# OpenBook_Schematic.net
KiCad netlist of a schematic drawn in EAGLE
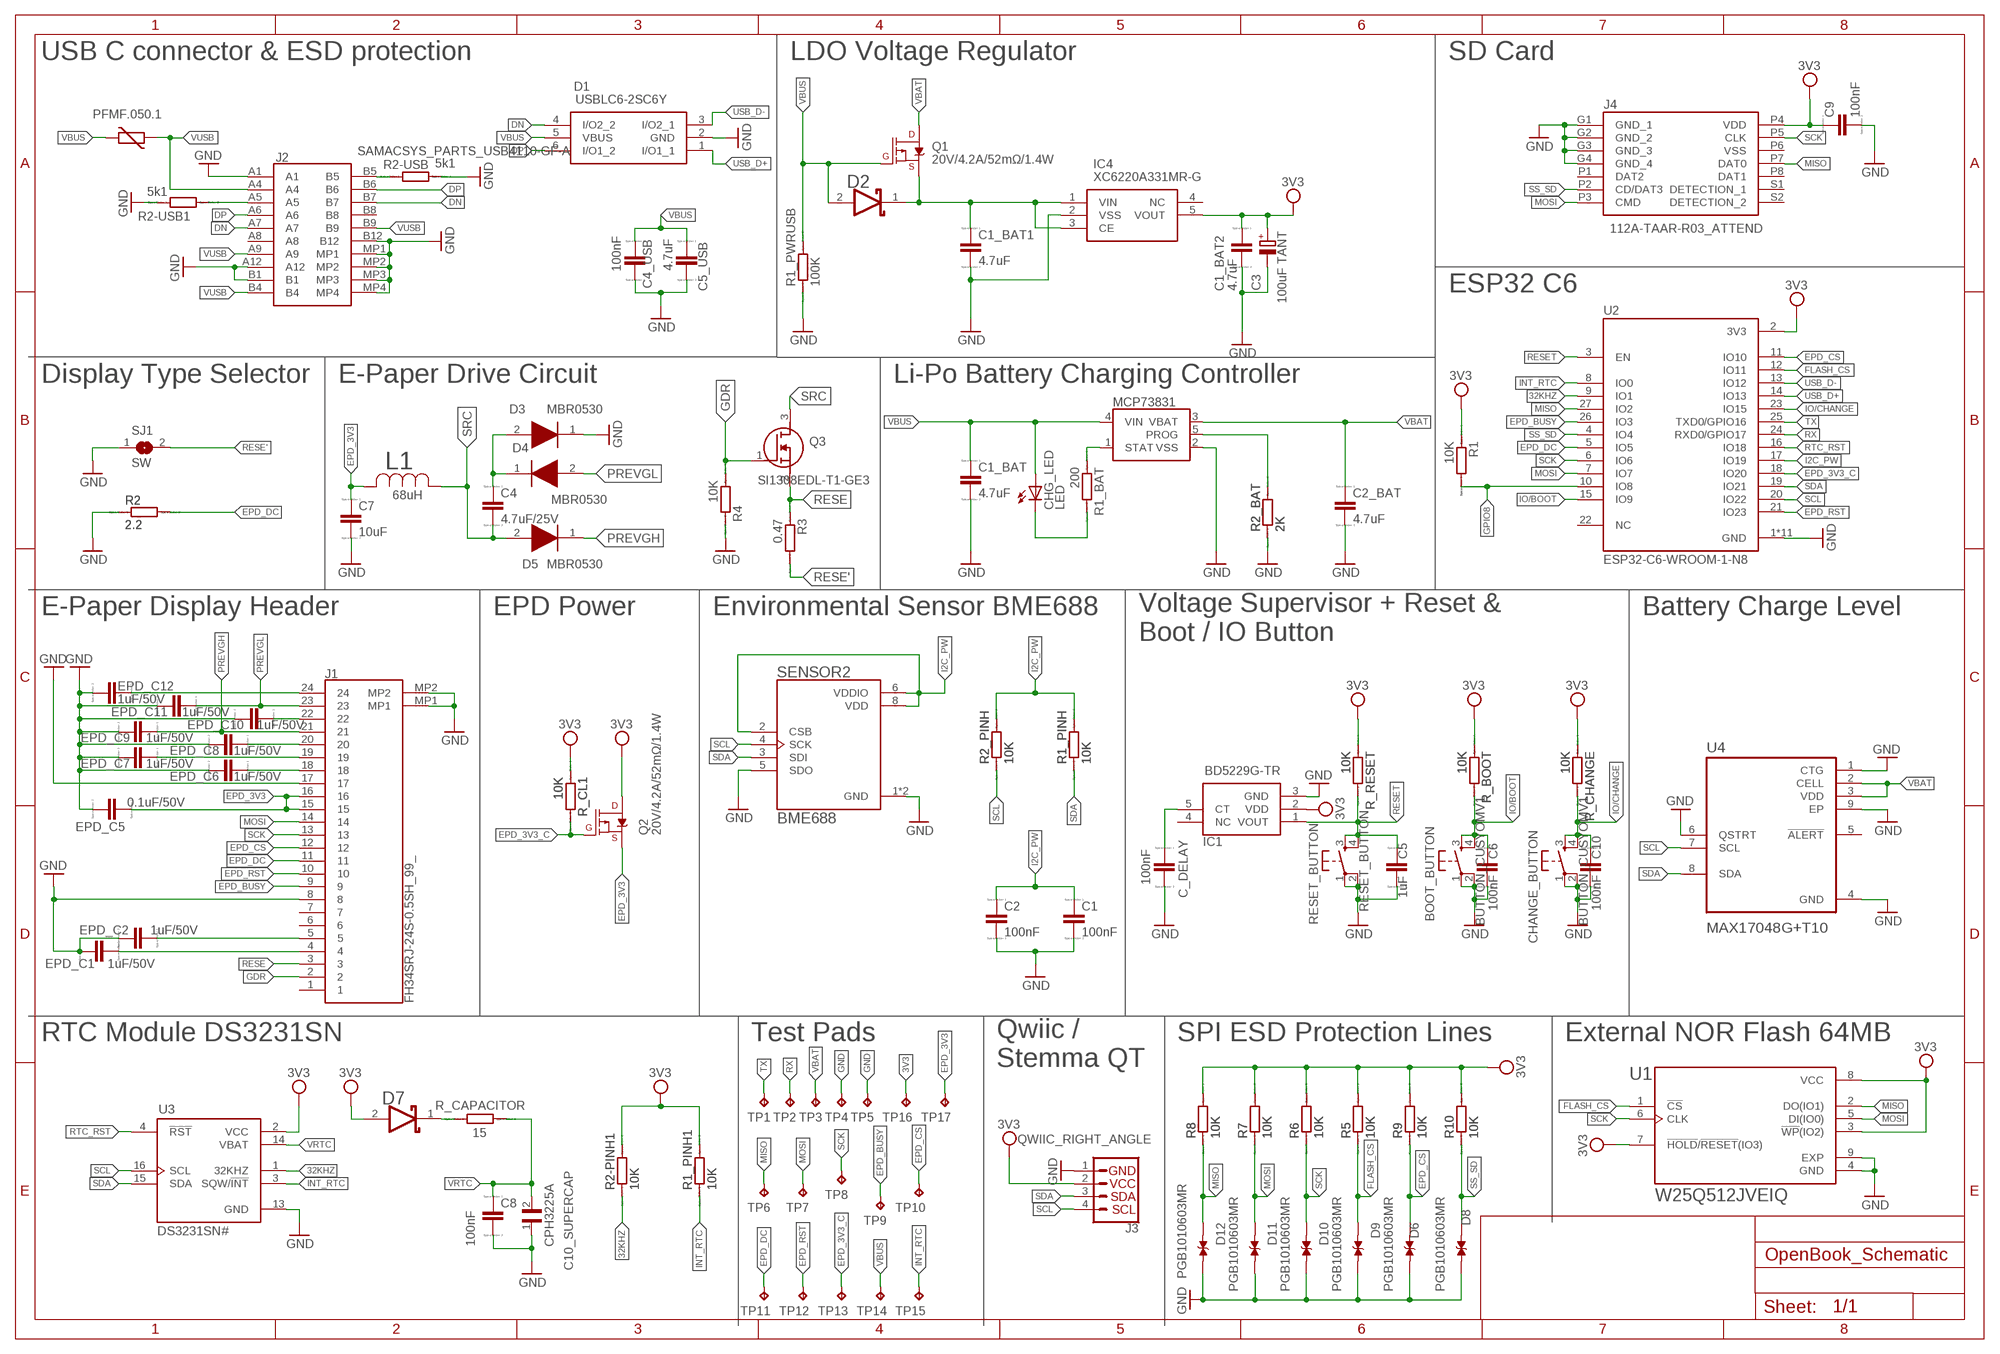
[diagram p0: schematic, sheet 1]

(export (version "E")
  (design (tool "Eeschema 10.0.6"))
  (components
    (comp (ref "BOOT_BUTTON")
      (value "BUTTON_CUSYOMV1")
      (footprint "eagle-import:MYBUTTON")
      (libsource (lib "eagle-import") (part "BUTTON_CUSYOMV1"))
    )
    (comp (ref "C1")
      (value "100nF")
      (footprint "eagle-import:EAGLE-LTSPICE_C0402")
      (libsource (lib "eagle-import") (part "EAGLE-LTSPICE_CC0402"))
    )
    (comp (ref "C1_BAT")
      (value "4.7uF")
      (footprint "eagle-import:EAGLE-LTSPICE_C0402")
      (libsource (lib "eagle-import") (part "EAGLE-LTSPICE_CC0402"))
    )
    (comp (ref "C1_BAT1")
      (value "4.7uF")
      (footprint "eagle-import:EAGLE-LTSPICE_C0402")
      (libsource (lib "eagle-import") (part "EAGLE-LTSPICE_CC0402"))
    )
    (comp (ref "C1_BAT2")
      (value "4.7uF")
      (footprint "eagle-import:EAGLE-LTSPICE_C0402")
      (libsource (lib "eagle-import") (part "EAGLE-LTSPICE_CC0402"))
    )
    (comp (ref "C2")
      (value "100nF")
      (footprint "eagle-import:EAGLE-LTSPICE_C0402")
      (libsource (lib "eagle-import") (part "EAGLE-LTSPICE_CC0402"))
    )
    (comp (ref "C2_BAT")
      (value "4.7uF")
      (footprint "eagle-import:EAGLE-LTSPICE_C0402")
      (libsource (lib "eagle-import") (part "EAGLE-LTSPICE_CC0402"))
    )
    (comp (ref "C3")
      (value "100uF TANT")
      (footprint "eagle-import:RCL_CT3528")
      (libsource (lib "eagle-import") (part "RCL_CPOL-EUCT3528"))
    )
    (comp (ref "C4")
      (value "4.7uF/25V")
      (footprint "eagle-import:EAGLE-LTSPICE_C0402")
      (libsource (lib "eagle-import") (part "EAGLE-LTSPICE_CC0402"))
    )
    (comp (ref "C4_USB")
      (value "100nF")
      (footprint "eagle-import:EAGLE-LTSPICE_C0402")
      (libsource (lib "eagle-import") (part "EAGLE-LTSPICE_CC0402"))
    )
    (comp (ref "C5")
      (value "1uF")
      (footprint "eagle-import:EAGLE-LTSPICE_C0402")
      (libsource (lib "eagle-import") (part "EAGLE-LTSPICE_CC0402"))
    )
    (comp (ref "C5_USB")
      (value "4.7uF")
      (footprint "eagle-import:EAGLE-LTSPICE_C0402")
      (libsource (lib "eagle-import") (part "EAGLE-LTSPICE_CC0402"))
    )
    (comp (ref "C6")
      (value "100nF")
      (footprint "eagle-import:EAGLE-LTSPICE_C0402")
      (libsource (lib "eagle-import") (part "EAGLE-LTSPICE_CC0402"))
    )
    (comp (ref "C7")
      (value "10uF")
      (footprint "eagle-import:EAGLE-LTSPICE_C0402")
      (libsource (lib "eagle-import") (part "EAGLE-LTSPICE_CC0402"))
    )
    (comp (ref "C8")
      (value "100nF")
      (footprint "eagle-import:EAGLE-LTSPICE_C0402")
      (libsource (lib "eagle-import") (part "EAGLE-LTSPICE_CC0402"))
    )
    (comp (ref "C9")
      (value "100nF")
      (footprint "eagle-import:EAGLE-LTSPICE_C0402")
      (libsource (lib "eagle-import") (part "EAGLE-LTSPICE_CC0402"))
    )
    (comp (ref "C10")
      (value "100nF")
      (footprint "eagle-import:EAGLE-LTSPICE_C0402")
      (libsource (lib "eagle-import") (part "EAGLE-LTSPICE_CC0402"))
    )
    (comp (ref "C10_SUPERCAP")
      (value "CPH3225A")
      (footprint "eagle-import:CAPCP3225X100N")
      (fields (field (name "MF") "Seiko Instruments"))
      (libsource (lib "eagle-import") (part "CPH3225A"))
    )
    (comp (ref "CHANGE_BUTTON")
      (value "BUTTON_CUSYOMV1")
      (footprint "eagle-import:MYBUTTON")
      (libsource (lib "eagle-import") (part "BUTTON_CUSYOMV1"))
    )
    (comp (ref "CHG_LED")
      (value "LED")
      (footprint "eagle-import:ADAFRUIT_CHIP-LED0603")
      (libsource (lib "eagle-import") (part "ADAFRUIT_LEDCHIP-LED0603"))
    )
    (comp (ref "C_DELAY")
      (value "100nF")
      (footprint "eagle-import:EAGLE-LTSPICE_C0402")
      (libsource (lib "eagle-import") (part "EAGLE-LTSPICE_CC0402"))
    )
    (comp (ref "D1")
      (value "USBLC6-2SC6Y")
      (footprint "eagle-import:SOT95P280X145-6N")
      (fields (field (name "MF") "STMicroelectronics"))
      (libsource (lib "eagle-import") (part "USBLC6-2SC6Y"))
    )
    (comp (ref "D2")
      (value "ESP32_WROVER_AVX---SD0805S020S1R0_AVX_SD0805S020S1R0_0_0AVX_SD0805S020S1R0_0_0")
      (footprint "eagle-import:ESP32_WROVER_AVX---SD0805S020S1R0_AVX_SD0805S020S1R0_0")
      (fields
        (field (name "DIGIKEY_PART_NUMBER") "478-7800-1-ND")
        (field (name "MF") "AVX")
        (field (name "MOUSER_PART_NUMBER") "581-SD0805S020S1R0")
      )
      (libsource (lib "eagle-import") (part "ESP32_WROVER_AVX---SD0805S020S1R0_AVX_SD0805S020S1R0_0_0AVX_SD0805S020S1R0_0_0"))
    )
    (comp (ref "D3")
      (value "MBR0530")
      (footprint "eagle-import:SOD3716X135N")
      (fields (field (name "MF") "ON Semiconductor"))
      (libsource (lib "eagle-import") (part "MBR0530"))
    )
    (comp (ref "D4")
      (value "MBR0530")
      (footprint "eagle-import:SOD3716X135N")
      (fields (field (name "MF") "ON Semiconductor"))
      (libsource (lib "eagle-import") (part "MBR0530"))
    )
    (comp (ref "D5")
      (value "MBR0530")
      (footprint "eagle-import:SOD3716X135N")
      (fields (field (name "MF") "ON Semiconductor"))
      (libsource (lib "eagle-import") (part "MBR0530"))
    )
    (comp (ref "D6")
      (value "PGB1010603MR")
      (footprint "eagle-import:DIOC1608X36N")
      (fields (field (name "MF") "Littelfuse Inc."))
      (libsource (lib "eagle-import") (part "PGB1010603MR"))
    )
    (comp (ref "D7")
      (value "ESP32_WROVER_AVX---SD0805S020S1R0_AVX_SD0805S020S1R0_0_0AVX_SD0805S020S1R0_0_0")
      (footprint "eagle-import:ESP32_WROVER_AVX---SD0805S020S1R0_AVX_SD0805S020S1R0_0")
      (fields
        (field (name "DIGIKEY_PART_NUMBER") "478-7800-1-ND")
        (field (name "MF") "AVX")
        (field (name "MOUSER_PART_NUMBER") "581-SD0805S020S1R0")
      )
      (libsource (lib "eagle-import") (part "ESP32_WROVER_AVX---SD0805S020S1R0_AVX_SD0805S020S1R0_0_0AVX_SD0805S020S1R0_0_0"))
    )
    (comp (ref "D8")
      (value "PGB1010603MR")
      (footprint "eagle-import:DIOC1608X36N")
      (fields (field (name "MF") "Littelfuse Inc."))
      (libsource (lib "eagle-import") (part "PGB1010603MR"))
    )
    (comp (ref "D9")
      (value "PGB1010603MR")
      (footprint "eagle-import:DIOC1608X36N")
      (fields (field (name "MF") "Littelfuse Inc."))
      (libsource (lib "eagle-import") (part "PGB1010603MR"))
    )
    (comp (ref "D10")
      (value "PGB1010603MR")
      (footprint "eagle-import:DIOC1608X36N")
      (fields (field (name "MF") "Littelfuse Inc."))
      (libsource (lib "eagle-import") (part "PGB1010603MR"))
    )
    (comp (ref "D11")
      (value "PGB1010603MR")
      (footprint "eagle-import:DIOC1608X36N")
      (fields (field (name "MF") "Littelfuse Inc."))
      (libsource (lib "eagle-import") (part "PGB1010603MR"))
    )
    (comp (ref "D12")
      (value "PGB1010603MR")
      (footprint "eagle-import:DIOC1608X36N")
      (fields (field (name "MF") "Littelfuse Inc."))
      (libsource (lib "eagle-import") (part "PGB1010603MR"))
    )
    (comp (ref "EPD_C1")
      (value "1uF/50V")
      (footprint "eagle-import:EAGLE-LTSPICE_C0402")
      (libsource (lib "eagle-import") (part "EAGLE-LTSPICE_CC0402"))
    )
    (comp (ref "EPD_C2")
      (value "1uF/50V")
      (footprint "eagle-import:EAGLE-LTSPICE_C0402")
      (libsource (lib "eagle-import") (part "EAGLE-LTSPICE_CC0402"))
    )
    (comp (ref "EPD_C5")
      (value "0.1uF/50V")
      (footprint "eagle-import:EAGLE-LTSPICE_C0402")
      (libsource (lib "eagle-import") (part "EAGLE-LTSPICE_CC0402"))
    )
    (comp (ref "EPD_C6")
      (value "1uF/50V")
      (footprint "eagle-import:EAGLE-LTSPICE_C0402")
      (libsource (lib "eagle-import") (part "EAGLE-LTSPICE_CC0402"))
    )
    (comp (ref "EPD_C7")
      (value "1uF/50V")
      (footprint "eagle-import:EAGLE-LTSPICE_C0402")
      (libsource (lib "eagle-import") (part "EAGLE-LTSPICE_CC0402"))
    )
    (comp (ref "EPD_C8")
      (value "1uF/50V")
      (footprint "eagle-import:EAGLE-LTSPICE_C0402")
      (libsource (lib "eagle-import") (part "EAGLE-LTSPICE_CC0402"))
    )
    (comp (ref "EPD_C9")
      (value "1uF/50V")
      (footprint "eagle-import:EAGLE-LTSPICE_C0402")
      (libsource (lib "eagle-import") (part "EAGLE-LTSPICE_CC0402"))
    )
    (comp (ref "EPD_C10")
      (value "1uF/50V")
      (footprint "eagle-import:EAGLE-LTSPICE_C0402")
      (libsource (lib "eagle-import") (part "EAGLE-LTSPICE_CC0402"))
    )
    (comp (ref "EPD_C11")
      (value "1uF/50V")
      (footprint "eagle-import:EAGLE-LTSPICE_C0402")
      (libsource (lib "eagle-import") (part "EAGLE-LTSPICE_CC0402"))
    )
    (comp (ref "EPD_C12")
      (value "1uF/50V")
      (footprint "eagle-import:EAGLE-LTSPICE_C0402")
      (libsource (lib "eagle-import") (part "EAGLE-LTSPICE_CC0402"))
    )
    (comp (ref "IC1")
      (value "BD5229G-TR")
      (footprint "eagle-import:SOT95P280X125-5N")
      (fields (field (name "MOUSER_PART_NUMBER") "755-BD5229G-TR"))
      (libsource (lib "eagle-import") (part "BD5229G-TR"))
    )
    (comp (ref "IC4")
      (value "XC6220A331MR-G")
      (footprint "eagle-import:SOT95P280X120-5N")
      (fields (field (name "MOUSER_PART_NUMBER") "865-XC6220A331MR-G"))
      (libsource (lib "eagle-import") (part "XC6220A331MR-G"))
    )
    (comp (ref "J1")
      (value "FH34SRJ-24S-0.5SH_99_")
      (footprint "eagle-import:FH34SRJ24S05SH99")
      (fields
        (field (name "MANUFACTURER_PART_NUMBER") "FH34SRJ-24S-0.5SH(99)")
        (field (name "MOUSER_PART_NUMBER") "798-FH34SRJ24S05SH99")
      )
      (libsource (lib "eagle-import") (part "FH34SRJ-24S-0.5SH_99_"))
    )
    (comp (ref "J2")
      (value "SAMACSYS_PARTS_USB4110-GF-A")
      (footprint "eagle-import:SAMACSYS_PARTS_USB4110GFA")
      (fields
        (field (name "MANUFACTURER_PART_NUMBER") "USB4110-GF-A")
        (field (name "MOUSER_PART_NUMBER") "640-USB4110-GF-A")
      )
      (libsource (lib "eagle-import") (part "SAMACSYS_PARTS_USB4110-GF-A"))
    )
    (comp (ref "J3")
      (value "QWIIC_RIGHT_ANGLE")
      (footprint "eagle-import:JST04_1MM_RA")
      (libsource (lib "eagle-import") (part "QWIIC_CONNECTORJS-1MM"))
    )
    (comp (ref "J4")
      (value "112A-TAAR-R03_ATTEND")
      (footprint "eagle-import:112ATAARR03ATTEND")
      (fields (field (name "MANUFACTURER_PART_NUMBER") "112A-TAAR-R03 ATTEND"))
      (libsource (lib "eagle-import") (part "112A-TAAR-R03_ATTEND"))
    )
    (comp (ref "L1")
      (value "68uH")
      (footprint "eagle-import:IND_4828-WE-TPC_WRE")
      (fields
        (field (name "MANUFACTURER_PART_NUMBER") "744043680")
        (field (name "COPYRIGHT") "Copyright (C) 2024 Ultra Librarian. All rights reserved.")
      )
      (libsource (lib "eagle-import") (part "744043680IND_4828-WE-TPC_WRE"))
    )
    (comp (ref "MCP73831")
      (value "ESP32_WROVER_SPARKFUN-IC-POWER_MCP73831")
      (footprint "eagle-import:ESP32_WROVER_SPARKFUN-IC-POWER_SOT23-5")
      (libsource (lib "eagle-import") (part "ESP32_WROVER_SPARKFUN-IC-POWER_MCP73831"))
    )
    (comp (ref "PFMF.050.1")
      (value "ESP32C6_VARISTORCN1812")
      (footprint "eagle-import:ESP32C6_VARISTOR_CT_CN1812")
      (libsource (lib "eagle-import") (part "ESP32C6_VARISTORCN1812"))
    )
    (comp (ref "Q1")
      (value "20V/4.2A/52mΩ/1.4W")
      (footprint "eagle-import:ESP32_WROVER_SPARKFUN-DISCRETESEMI_SOT23-3")
      (libsource (lib "eagle-import") (part "ESP32_WROVER_SPARKFUN-DISCRETESEMI_MOSFET_PCH-DMG2305UX-7"))
    )
    (comp (ref "Q2")
      (value "20V/4.2A/52mΩ/1.4W")
      (footprint "eagle-import:ESP32_WROVER_SPARKFUN-DISCRETESEMI_SOT23-3")
      (libsource (lib "eagle-import") (part "ESP32_WROVER_SPARKFUN-DISCRETESEMI_MOSFET_PCH-DMG2305UX-7"))
    )
    (comp (ref "Q3")
      (value "SI1308EDL-T1-GE3")
      (footprint "eagle-import:SOT65P210X110-3N")
      (fields (field (name "MF") "Vishay Siliconix"))
      (libsource (lib "eagle-import") (part "SI1308EDL-T1-GE3"))
    )
    (comp (ref "R1")
      (value "10K")
      (footprint "eagle-import:ESP32_WROVER_EAGLE-LTSPICE_R0402")
      (libsource (lib "eagle-import") (part "ESP32_WROVER_EAGLE-LTSPICE_RR0402"))
    )
    (comp (ref "R1_BAT")
      (value "200")
      (footprint "eagle-import:ESP32_WROVER_EAGLE-LTSPICE_R0402")
      (libsource (lib "eagle-import") (part "ESP32_WROVER_EAGLE-LTSPICE_RR0402"))
    )
    (comp (ref "R1_PINH")
      (value "10K")
      (footprint "eagle-import:ESP32_WROVER_EAGLE-LTSPICE_R0402")
      (libsource (lib "eagle-import") (part "ESP32_WROVER_EAGLE-LTSPICE_RR0402"))
    )
    (comp (ref "R1_PINH1")
      (value "10K")
      (footprint "eagle-import:ESP32_WROVER_EAGLE-LTSPICE_R0402")
      (libsource (lib "eagle-import") (part "ESP32_WROVER_EAGLE-LTSPICE_RR0402"))
    )
    (comp (ref "R1_PWRUSB")
      (value "100K")
      (footprint "eagle-import:ESP32_WROVER_EAGLE-LTSPICE_R0402")
      (libsource (lib "eagle-import") (part "ESP32_WROVER_EAGLE-LTSPICE_RR0402"))
    )
    (comp (ref "R2")
      (value "2.2")
      (footprint "eagle-import:ESP32_WROVER_EAGLE-LTSPICE_R0402")
      (libsource (lib "eagle-import") (part "ESP32_WROVER_EAGLE-LTSPICE_RR0402"))
    )
    (comp (ref "R2-PINH1")
      (value "10K")
      (footprint "eagle-import:ESP32_WROVER_EAGLE-LTSPICE_R0402")
      (libsource (lib "eagle-import") (part "ESP32_WROVER_EAGLE-LTSPICE_RR0402"))
    )
    (comp (ref "R2-USB")
      (value "5k1")
      (footprint "eagle-import:ESP32_WROVER_EAGLE-LTSPICE_R0402")
      (libsource (lib "eagle-import") (part "ESP32_WROVER_EAGLE-LTSPICE_RR0402"))
    )
    (comp (ref "R2-USB1")
      (value "5k1")
      (footprint "eagle-import:ESP32_WROVER_EAGLE-LTSPICE_R0402")
      (libsource (lib "eagle-import") (part "ESP32_WROVER_EAGLE-LTSPICE_RR0402"))
    )
    (comp (ref "R2_BAT")
      (value "2K")
      (footprint "eagle-import:ESP32_WROVER_EAGLE-LTSPICE_R0402")
      (libsource (lib "eagle-import") (part "ESP32_WROVER_EAGLE-LTSPICE_RR0402"))
    )
    (comp (ref "R2_PINH")
      (value "10K")
      (footprint "eagle-import:ESP32_WROVER_EAGLE-LTSPICE_R0402")
      (libsource (lib "eagle-import") (part "ESP32_WROVER_EAGLE-LTSPICE_RR0402"))
    )
    (comp (ref "R3")
      (value "0.47")
      (footprint "eagle-import:ESP32_WROVER_EAGLE-LTSPICE_R0402")
      (libsource (lib "eagle-import") (part "ESP32_WROVER_EAGLE-LTSPICE_RR0402"))
    )
    (comp (ref "R4")
      (value "10K")
      (footprint "eagle-import:ESP32_WROVER_EAGLE-LTSPICE_R0402")
      (libsource (lib "eagle-import") (part "ESP32_WROVER_EAGLE-LTSPICE_RR0402"))
    )
    (comp (ref "R5")
      (value "10K")
      (footprint "eagle-import:ESP32_WROVER_EAGLE-LTSPICE_R0402")
      (libsource (lib "eagle-import") (part "ESP32_WROVER_EAGLE-LTSPICE_RR0402"))
    )
    (comp (ref "R6")
      (value "10K")
      (footprint "eagle-import:ESP32_WROVER_EAGLE-LTSPICE_R0402")
      (libsource (lib "eagle-import") (part "ESP32_WROVER_EAGLE-LTSPICE_RR0402"))
    )
    (comp (ref "R7")
      (value "10K")
      (footprint "eagle-import:ESP32_WROVER_EAGLE-LTSPICE_R0402")
      (libsource (lib "eagle-import") (part "ESP32_WROVER_EAGLE-LTSPICE_RR0402"))
    )
    (comp (ref "R8")
      (value "10K")
      (footprint "eagle-import:ESP32_WROVER_EAGLE-LTSPICE_R0402")
      (libsource (lib "eagle-import") (part "ESP32_WROVER_EAGLE-LTSPICE_RR0402"))
    )
    (comp (ref "R9")
      (value "10K")
      (footprint "eagle-import:ESP32_WROVER_EAGLE-LTSPICE_R0402")
      (libsource (lib "eagle-import") (part "ESP32_WROVER_EAGLE-LTSPICE_RR0402"))
    )
    (comp (ref "R10")
      (value "10K")
      (footprint "eagle-import:ESP32_WROVER_EAGLE-LTSPICE_R0402")
      (libsource (lib "eagle-import") (part "ESP32_WROVER_EAGLE-LTSPICE_RR0402"))
    )
    (comp (ref "RESET_BUTTON")
      (value "RESET_BUTTON")
      (footprint "eagle-import:MYBUTTON")
      (libsource (lib "eagle-import") (part "BUTTON_CUSYOMV1"))
    )
    (comp (ref "R_BOOT")
      (value "10K")
      (footprint "eagle-import:ESP32_WROVER_EAGLE-LTSPICE_R0402")
      (libsource (lib "eagle-import") (part "ESP32_WROVER_EAGLE-LTSPICE_RR0402"))
    )
    (comp (ref "R_CAPACITOR")
      (value "15")
      (footprint "eagle-import:ESP32_WROVER_EAGLE-LTSPICE_R0402")
      (libsource (lib "eagle-import") (part "ESP32_WROVER_EAGLE-LTSPICE_RR0402"))
    )
    (comp (ref "R_CHANGE")
      (value "10K")
      (footprint "eagle-import:ESP32_WROVER_EAGLE-LTSPICE_R0402")
      (libsource (lib "eagle-import") (part "ESP32_WROVER_EAGLE-LTSPICE_RR0402"))
    )
    (comp (ref "R_CL1")
      (value "10K")
      (footprint "eagle-import:ESP32_WROVER_EAGLE-LTSPICE_R0402")
      (libsource (lib "eagle-import") (part "ESP32_WROVER_EAGLE-LTSPICE_RR0402"))
    )
    (comp (ref "R_RESET")
      (value "10K")
      (footprint "eagle-import:ESP32_WROVER_EAGLE-LTSPICE_R0402")
      (libsource (lib "eagle-import") (part "ESP32_WROVER_EAGLE-LTSPICE_RR0402"))
    )
    (comp (ref "SENSOR2")
      (value "BME688")
      (footprint "eagle-import:ESP32_WROVER_BME680_PSON80P300X300X100-8N")
      (fields (field (name "MF") "Bosch Sensortec") (field (name "MP") "BME680"))
      (libsource (lib "eagle-import") (part "ESP32_WROVER_BME680_BME680"))
    )
    (comp (ref "SJ1") (value "SW") (footprint "eagle-import:SJ") (libsource (lib "eagle-import") (part "SJ")))
    (comp (ref "TP1")
      (value "TPTP20R")
      (footprint "eagle-import:TP20R")
      (libsource (lib "eagle-import") (part "TPTP20R"))
    )
    (comp (ref "TP2")
      (value "TPTP20R")
      (footprint "eagle-import:TP20R")
      (libsource (lib "eagle-import") (part "TPTP20R"))
    )
    (comp (ref "TP3")
      (value "TPTP20R")
      (footprint "eagle-import:TP20R")
      (libsource (lib "eagle-import") (part "TPTP20R"))
    )
    (comp (ref "TP4")
      (value "TPTP20R")
      (footprint "eagle-import:TP20R")
      (libsource (lib "eagle-import") (part "TPTP20R"))
    )
    (comp (ref "TP5")
      (value "TPTP20R")
      (footprint "eagle-import:TP20R")
      (libsource (lib "eagle-import") (part "TPTP20R"))
    )
    (comp (ref "TP6")
      (value "TPTP20R")
      (footprint "eagle-import:TP20R")
      (libsource (lib "eagle-import") (part "TPTP20R"))
    )
    (comp (ref "TP7")
      (value "TPTP20R")
      (footprint "eagle-import:TP20R")
      (libsource (lib "eagle-import") (part "TPTP20R"))
    )
    (comp (ref "TP8")
      (value "TPTP20R")
      (footprint "eagle-import:TP20R")
      (libsource (lib "eagle-import") (part "TPTP20R"))
    )
    (comp (ref "TP9")
      (value "TPTP20R")
      (footprint "eagle-import:TP20R")
      (libsource (lib "eagle-import") (part "TPTP20R"))
    )
    (comp (ref "TP10")
      (value "TPTP20R")
      (footprint "eagle-import:TP20R")
      (libsource (lib "eagle-import") (part "TPTP20R"))
    )
    (comp (ref "TP11")
      (value "TPTP20R")
      (footprint "eagle-import:TP20R")
      (libsource (lib "eagle-import") (part "TPTP20R"))
    )
    (comp (ref "TP12")
      (value "TPTP20R")
      (footprint "eagle-import:TP20R")
      (libsource (lib "eagle-import") (part "TPTP20R"))
    )
    (comp (ref "TP13")
      (value "TPTP20R")
      (footprint "eagle-import:TP20R")
      (libsource (lib "eagle-import") (part "TPTP20R"))
    )
    (comp (ref "TP14")
      (value "TPTP20R")
      (footprint "eagle-import:TP20R")
      (libsource (lib "eagle-import") (part "TPTP20R"))
    )
    (comp (ref "TP15")
      (value "TPTP20R")
      (footprint "eagle-import:TP20R")
      (libsource (lib "eagle-import") (part "TPTP20R"))
    )
    (comp (ref "TP16")
      (value "TPTP20R")
      (footprint "eagle-import:TP20R")
      (libsource (lib "eagle-import") (part "TPTP20R"))
    )
    (comp (ref "TP17")
      (value "TPTP20R")
      (footprint "eagle-import:TP20R")
      (libsource (lib "eagle-import") (part "TPTP20R"))
    )
    (comp (ref "U1")
      (value "W25Q512JVEIQ")
      (footprint "eagle-import:SON127P600X800X80-9N")
      (fields (field (name "MF") "Winbond Electronics"))
      (libsource (lib "eagle-import") (part "W25Q512JVEIQ"))
    )
    (comp (ref "U2")
      (value "ESP32-C6-WROOM-1-N8")
      (footprint "eagle-import:XCVR_ESP32-C6-WROOM-1-N8")
      (fields (field (name "MF") "Espressif Systems"))
      (libsource (lib "eagle-import") (part "ESP32-C6-WROOM-1-N8"))
    )
    (comp (ref "U3")
      (value "DS3231SN#")
      (footprint "eagle-import:SOIC127P1032X265-16N")
      (fields (field (name "MF") "Analog Devices"))
      (libsource (lib "eagle-import") (part "DS3231SN#"))
    )
    (comp (ref "U4")
      (value "MAX17048G+T10")
      (footprint "eagle-import:SON50P200X200X80-9N")
      (fields (field (name "MF") "Analog Devices"))
      (libsource (lib "eagle-import") (part "MAX17048G+T10"))
    )
  )
  (nets
    (net (code "1") (name "3V3") (class "Default")
      (node (ref "C1_BAT2") (pin "1") (pinfunction "1_1") (pintype "passive"))
      (node (ref "C3") (pin "+") (pinfunction "+_+") (pintype "passive"))
      (node (ref "C9") (pin "1") (pinfunction "1_1") (pintype "passive"))
      (node (ref "D7") (pin "2") (pinfunction "ANODE_2") (pintype "bidirectional"))
      (node (ref "IC1") (pin "2") (pinfunction "VDD_2") (pintype "bidirectional"))
      (node (ref "IC4") (pin "5") (pinfunction "VOUT_5") (pintype "bidirectional"))
      (node (ref "J3") (pin "2") (pinfunction "2_2") (pintype "power_in"))
      (node (ref "J4") (pin "P4") (pinfunction "VDD_P4") (pintype "bidirectional"))
      (node (ref "Q2") (pin "3") (pinfunction "D_3") (pintype "bidirectional"))
      (node (ref "R1") (pin "1") (pinfunction "1_1") (pintype "passive"))
      (node (ref "R10") (pin "2") (pinfunction "2_2") (pintype "passive"))
      (node (ref "R1_PINH1") (pin "2") (pinfunction "2_2") (pintype "passive"))
      (node (ref "R2-PINH1") (pin "2") (pinfunction "2_2") (pintype "passive"))
      (node (ref "R5") (pin "2") (pinfunction "2_2") (pintype "passive"))
      (node (ref "R6") (pin "2") (pinfunction "2_2") (pintype "passive"))
      (node (ref "R7") (pin "2") (pinfunction "2_2") (pintype "passive"))
      (node (ref "R8") (pin "2") (pinfunction "2_2") (pintype "passive"))
      (node (ref "R9") (pin "2") (pinfunction "2_2") (pintype "passive"))
      (node (ref "R_BOOT") (pin "1") (pinfunction "1_1") (pintype "passive"))
      (node (ref "R_CHANGE") (pin "1") (pinfunction "1_1") (pintype "passive"))
      (node (ref "R_CL1") (pin "1") (pinfunction "1_1") (pintype "passive"))
      (node (ref "R_RESET") (pin "1") (pinfunction "1_1") (pintype "passive"))
      (node (ref "TP16") (pin "TP") (pinfunction "TP_TP") (pintype "input"))
      (node (ref "U1") (pin "3") (pinfunction "~{WP}(IO2)_3") (pintype "bidirectional"))
      (node (ref "U1") (pin "7") (pinfunction "~{HOLD}/~{RESET}(IO3)_7") (pintype "bidirectional"))
      (node (ref "U1") (pin "8") (pinfunction "VCC_8") (pintype "power_in"))
      (node (ref "U2") (pin "2") (pinfunction "3V3_2") (pintype "power_in"))
      (node (ref "U3") (pin "2") (pinfunction "VCC_2") (pintype "power_in"))
    )
    (net (code "2") (name "32KHZ") (class "Default")
      (node (ref "R2-PINH1") (pin "1") (pinfunction "1_1") (pintype "passive"))
      (node (ref "U2") (pin "9") (pinfunction "IO1_9") (pintype "bidirectional"))
      (node (ref "U3") (pin "1") (pinfunction "32KHZ_1") (pintype "output"))
    )
    (net (code "3") (name "DN") (class "Default")
      (node (ref "D1") (pin "4") (pinfunction "I/O2_2_4") (pintype "bidirectional"))
      (node (ref "J2") (pin "A7") (pinfunction "A7_A7") (pintype "bidirectional"))
      (node (ref "J2") (pin "B7") (pinfunction "B7_B7") (pintype "bidirectional"))
    )
    (net (code "4") (name "DP") (class "Default")
      (node (ref "D1") (pin "6") (pinfunction "I/O1_2_6") (pintype "bidirectional"))
      (node (ref "J2") (pin "A6") (pinfunction "A6_A6") (pintype "bidirectional"))
      (node (ref "J2") (pin "B6") (pinfunction "B6_B6") (pintype "bidirectional"))
    )
    (net (code "5") (name "EPD_3V3") (class "Default")
      (node (ref "C7") (pin "1") (pinfunction "1_1") (pintype "passive"))
      (node (ref "EPD_C5") (pin "1") (pinfunction "1_1") (pintype "passive"))
      (node (ref "J1") (pin "15") (pinfunction "15_15") (pintype "bidirectional"))
      (node (ref "J1") (pin "16") (pinfunction "16_16") (pintype "bidirectional"))
      (node (ref "L1") (pin "2") (pinfunction "2_2") (pintype "passive"))
      (node (ref "Q2") (pin "2") (pinfunction "S_2") (pintype "bidirectional"))
      (node (ref "TP17") (pin "TP") (pinfunction "TP_TP") (pintype "input"))
    )
    (net (code "6") (name "EPD_3V3_C") (class "Default")
      (node (ref "Q2") (pin "1") (pinfunction "G_1") (pintype "bidirectional"))
      (node (ref "R_CL1") (pin "2") (pinfunction "2_2") (pintype "passive"))
      (node (ref "TP13") (pin "TP") (pinfunction "TP_TP") (pintype "input"))
      (node (ref "U2") (pin "18") (pinfunction "IO20_18") (pintype "bidirectional"))
    )
    (net (code "7") (name "EPD_BUSY") (class "Default")
      (node (ref "J1") (pin "9") (pinfunction "9_9") (pintype "bidirectional"))
      (node (ref "TP9") (pin "TP") (pinfunction "TP_TP") (pintype "input"))
      (node (ref "U2") (pin "26") (pinfunction "IO3_26") (pintype "bidirectional"))
    )
    (net (code "8") (name "EPD_CS") (class "Default")
      (node (ref "D6") (pin "1") (pinfunction "1_1") (pintype "passive"))
      (node (ref "J1") (pin "12") (pinfunction "12_12") (pintype "bidirectional"))
      (node (ref "R9") (pin "1") (pinfunction "1_1") (pintype "passive"))
      (node (ref "TP10") (pin "TP") (pinfunction "TP_TP") (pintype "input"))
      (node (ref "U2") (pin "11") (pinfunction "IO10_11") (pintype "bidirectional"))
    )
    (net (code "9") (name "EPD_DC") (class "Default")
      (node (ref "J1") (pin "11") (pinfunction "11_11") (pintype "bidirectional"))
      (node (ref "R2") (pin "2") (pinfunction "2_2") (pintype "passive"))
      (node (ref "TP11") (pin "TP") (pinfunction "TP_TP") (pintype "input"))
      (node (ref "U2") (pin "5") (pinfunction "IO5_5") (pintype "bidirectional"))
    )
    (net (code "10") (name "EPD_RST") (class "Default")
      (node (ref "J1") (pin "10") (pinfunction "10_10") (pintype "bidirectional"))
      (node (ref "TP12") (pin "TP") (pinfunction "TP_TP") (pintype "input"))
      (node (ref "U2") (pin "21") (pinfunction "IO23_21") (pintype "bidirectional"))
    )
    (net (code "11") (name "FLASH_CS") (class "Default")
      (node (ref "D9") (pin "1") (pinfunction "1_1") (pintype "passive"))
      (node (ref "R5") (pin "1") (pinfunction "1_1") (pintype "passive"))
      (node (ref "U1") (pin "1") (pinfunction "~{CS}_1") (pintype "input"))
      (node (ref "U2") (pin "12") (pinfunction "IO11_12") (pintype "bidirectional"))
    )
    (net (code "12") (name "GDR") (class "Default")
      (node (ref "J1") (pin "2") (pinfunction "2_2") (pintype "bidirectional"))
      (node (ref "Q3") (pin "1") (pinfunction "G_1") (pintype "bidirectional"))
      (node (ref "R4") (pin "1") (pinfunction "1_1") (pintype "passive"))
    )
    (net (code "13") (name "GND") (class "Default")
      (node (ref "BOOT_BUTTON") (pin "1") (pinfunction "1_1") (pintype "passive"))
      (node (ref "BOOT_BUTTON") (pin "2") (pinfunction "2_2") (pintype "passive"))
      (node (ref "C1") (pin "2") (pinfunction "2_2") (pintype "passive"))
      (node (ref "C10") (pin "2") (pinfunction "2_2") (pintype "passive"))
      (node (ref "C10_SUPERCAP") (pin "1") (pinfunction "1_1") (pintype "passive"))
      (node (ref "C1_BAT") (pin "2") (pinfunction "2_2") (pintype "passive"))
      (node (ref "C1_BAT1") (pin "2") (pinfunction "2_2") (pintype "passive"))
      (node (ref "C1_BAT2") (pin "2") (pinfunction "2_2") (pintype "passive"))
      (node (ref "C2") (pin "2") (pinfunction "2_2") (pintype "passive"))
      (node (ref "C2_BAT") (pin "2") (pinfunction "2_2") (pintype "passive"))
      (node (ref "C3") (pin "-") (pinfunction "-_-") (pintype "passive"))
      (node (ref "C4_USB") (pin "2") (pinfunction "2_2") (pintype "passive"))
      (node (ref "C5") (pin "2") (pinfunction "2_2") (pintype "passive"))
      (node (ref "C5_USB") (pin "2") (pinfunction "2_2") (pintype "passive"))
      (node (ref "C6") (pin "2") (pinfunction "2_2") (pintype "passive"))
      (node (ref "C7") (pin "2") (pinfunction "2_2") (pintype "passive"))
      (node (ref "C8") (pin "2") (pinfunction "2_2") (pintype "passive"))
      (node (ref "C9") (pin "2") (pinfunction "2_2") (pintype "passive"))
      (node (ref "CHANGE_BUTTON") (pin "1") (pinfunction "1_1") (pintype "passive"))
      (node (ref "CHANGE_BUTTON") (pin "2") (pinfunction "2_2") (pintype "passive"))
      (node (ref "C_DELAY") (pin "2") (pinfunction "2_2") (pintype "passive"))
      (node (ref "D1") (pin "2") (pinfunction "GND_2") (pintype "bidirectional"))
      (node (ref "D10") (pin "2") (pinfunction "2_2") (pintype "passive"))
      (node (ref "D11") (pin "2") (pinfunction "2_2") (pintype "passive"))
      (node (ref "D12") (pin "1") (pinfunction "1_1") (pintype "passive"))
      (node (ref "D3") (pin "1") (pinfunction "K_1") (pintype "bidirectional"))
      (node (ref "D6") (pin "2") (pinfunction "2_2") (pintype "passive"))
      (node (ref "D8") (pin "2") (pinfunction "2_2") (pintype "passive"))
      (node (ref "D9") (pin "2") (pinfunction "2_2") (pintype "passive"))
      (node (ref "EPD_C1") (pin "2") (pinfunction "2_2") (pintype "passive"))
      (node (ref "EPD_C10") (pin "2") (pinfunction "2_2") (pintype "passive"))
      (node (ref "EPD_C11") (pin "2") (pinfunction "2_2") (pintype "passive"))
      (node (ref "EPD_C12") (pin "2") (pinfunction "2_2") (pintype "passive"))
      (node (ref "EPD_C2") (pin "2") (pinfunction "2_2") (pintype "passive"))
      (node (ref "EPD_C5") (pin "2") (pinfunction "2_2") (pintype "passive"))
      (node (ref "EPD_C6") (pin "2") (pinfunction "2_2") (pintype "passive"))
      (node (ref "EPD_C7") (pin "2") (pinfunction "2_2") (pintype "passive"))
      (node (ref "EPD_C8") (pin "2") (pinfunction "2_2") (pintype "passive"))
      (node (ref "EPD_C9") (pin "2") (pinfunction "2_2") (pintype "passive"))
      (node (ref "IC1") (pin "3") (pinfunction "GND_3") (pintype "bidirectional"))
      (node (ref "IC4") (pin "2") (pinfunction "VSS_2") (pintype "bidirectional"))
      (node (ref "J1") (pin "17") (pinfunction "17_17") (pintype "bidirectional"))
      (node (ref "J1") (pin "8") (pinfunction "8_8") (pintype "bidirectional"))
      (node (ref "J1") (pin "MP1") (pinfunction "MP1_MP1") (pintype "bidirectional"))
      (node (ref "J1") (pin "MP2") (pinfunction "MP2_MP2") (pintype "bidirectional"))
      (node (ref "J2") (pin "A1") (pinfunction "A1_A1") (pintype "bidirectional"))
      (node (ref "J2") (pin "A12") (pinfunction "A12_A12") (pintype "bidirectional"))
      (node (ref "J2") (pin "B1") (pinfunction "B1_B1") (pintype "bidirectional"))
      (node (ref "J2") (pin "B12") (pinfunction "B12_B12") (pintype "bidirectional"))
      (node (ref "J2") (pin "MP1") (pinfunction "MP1_MP1") (pintype "bidirectional"))
      (node (ref "J2") (pin "MP2") (pinfunction "MP2_MP2") (pintype "bidirectional"))
      (node (ref "J2") (pin "MP3") (pinfunction "MP3_MP3") (pintype "bidirectional"))
      (node (ref "J2") (pin "MP4") (pinfunction "MP4_MP4") (pintype "bidirectional"))
      (node (ref "J3") (pin "1") (pinfunction "1_1") (pintype "power_in"))
      (node (ref "J4") (pin "G1") (pinfunction "GND_1_G1") (pintype "bidirectional"))
      (node (ref "J4") (pin "G2") (pinfunction "GND_2_G2") (pintype "bidirectional"))
      (node (ref "J4") (pin "G3") (pinfunction "GND_3_G3") (pintype "bidirectional"))
      (node (ref "J4") (pin "G4") (pinfunction "GND_4_G4") (pintype "bidirectional"))
      (node (ref "MCP73831") (pin "2") (pinfunction "VSS_2") (pintype "power_in"))
      (node (ref "R1_PWRUSB") (pin "1") (pinfunction "1_1") (pintype "passive"))
      (node (ref "R2") (pin "1") (pinfunction "1_1") (pintype "passive"))
      (node (ref "R2-USB") (pin "2") (pinfunction "2_2") (pintype "passive"))
      (node (ref "R2-USB1") (pin "1") (pinfunction "1_1") (pintype "passive"))
      (node (ref "R2_BAT") (pin "1") (pinfunction "1_1") (pintype "passive"))
      (node (ref "R4") (pin "2") (pinfunction "2_2") (pintype "passive"))
      (node (ref "RESET_BUTTON") (pin "1") (pinfunction "1_1") (pintype "passive"))
      (node (ref "RESET_BUTTON") (pin "2") (pinfunction "2_2") (pintype "passive"))
      (node (ref "SENSOR2") (pin "1") (pinfunction "GND_1") (pintype "power_in"))
      (node (ref "SENSOR2") (pin "5") (pinfunction "SDO_5") (pintype "bidirectional"))
      (node (ref "SENSOR2") (pin "7") (pinfunction "GND_7") (pintype "power_in"))
      (node (ref "SJ1") (pin "1") (pinfunction "1_1") (pintype "passive"))
      (node (ref "TP4") (pin "TP") (pinfunction "TP_TP") (pintype "input"))
      (node (ref "TP5") (pin "TP") (pinfunction "TP_TP") (pintype "input"))
      (node (ref "U1") (pin "4") (pinfunction "GND_4") (pintype "power_in"))
      (node (ref "U1") (pin "9") (pinfunction "EXP_9") (pintype "passive"))
      (node (ref "U2") (pin "1") (pinfunction "GND_1") (pintype "power_in"))
      (node (ref "U2") (pin "28") (pinfunction "GND_28") (pintype "power_in"))
      (node (ref "U2") (pin "29_1") (pinfunction "GND_29_1") (pintype "power_in"))
      (node (ref "U2") (pin "29_2") (pinfunction "GND_29_2") (pintype "power_in"))
      (node (ref "U2") (pin "29_3") (pinfunction "GND_29_3") (pintype "power_in"))
      (node (ref "U2") (pin "29_4") (pinfunction "GND_29_4") (pintype "power_in"))
      (node (ref "U2") (pin "29_5") (pinfunction "GND_29_5") (pintype "power_in"))
      (node (ref "U2") (pin "29_6") (pinfunction "GND_29_6") (pintype "power_in"))
      (node (ref "U2") (pin "29_7") (pinfunction "GND_29_7") (pintype "power_in"))
      (node (ref "U2") (pin "29_8") (pinfunction "GND_29_8") (pintype "power_in"))
      (node (ref "U2") (pin "29_9") (pinfunction "GND_29_9") (pintype "power_in"))
      (node (ref "U3") (pin "13") (pinfunction "GND_13") (pintype "power_in"))
      (node (ref "U4") (pin "1") (pinfunction "CTG_1") (pintype "power_in"))
      (node (ref "U4") (pin "4") (pinfunction "GND_4") (pintype "power_in"))
      (node (ref "U4") (pin "6") (pinfunction "QSTRT_6") (pintype "input"))
      (node (ref "U4") (pin "9") (pinfunction "EP_9") (pintype "power_in"))
    )
    (net (code "14") (name "GPIO8") (class "Default")
      (node (ref "R1") (pin "2") (pinfunction "2_2") (pintype "passive"))
      (node (ref "U2") (pin "10") (pinfunction "IO8_10") (pintype "bidirectional"))
    )
    (net (code "15") (name "I2C_PW") (class "Default")
      (node (ref "C1") (pin "1") (pinfunction "1_1") (pintype "passive"))
      (node (ref "C2") (pin "1") (pinfunction "1_1") (pintype "passive"))
      (node (ref "R1_PINH") (pin "2") (pinfunction "2_2") (pintype "passive"))
      (node (ref "R2_PINH") (pin "2") (pinfunction "2_2") (pintype "passive"))
      (node (ref "SENSOR2") (pin "2") (pinfunction "CSB_2") (pintype "input"))
      (node (ref "SENSOR2") (pin "6") (pinfunction "VDDIO_6") (pintype "power_in"))
      (node (ref "SENSOR2") (pin "8") (pinfunction "VDD_8") (pintype "power_in"))
      (node (ref "U2") (pin "17") (pinfunction "IO19_17") (pintype "bidirectional"))
    )
    (net (code "16") (name "INT_RTC") (class "Default")
      (node (ref "R1_PINH1") (pin "1") (pinfunction "1_1") (pintype "passive"))
      (node (ref "TP15") (pin "TP") (pinfunction "TP_TP") (pintype "input"))
      (node (ref "U2") (pin "8") (pinfunction "IO0_8") (pintype "bidirectional"))
      (node (ref "U3") (pin "3") (pinfunction "SQW/~{INT}_3") (pintype "output"))
    )
    (net (code "17") (name "IO{slash}BOOT") (class "Default")
      (node (ref "BOOT_BUTTON") (pin "3") (pinfunction "3_3") (pintype "passive"))
      (node (ref "BOOT_BUTTON") (pin "4") (pinfunction "4_4") (pintype "passive"))
      (node (ref "C6") (pin "1") (pinfunction "1_1") (pintype "passive"))
      (node (ref "R_BOOT") (pin "2") (pinfunction "2_2") (pintype "passive"))
      (node (ref "U2") (pin "15") (pinfunction "IO9_15") (pintype "bidirectional"))
    )
    (net (code "18") (name "IO{slash}CHANGE") (class "Default")
      (node (ref "C10") (pin "1") (pinfunction "1_1") (pintype "passive"))
      (node (ref "CHANGE_BUTTON") (pin "3") (pinfunction "3_3") (pintype "passive"))
      (node (ref "CHANGE_BUTTON") (pin "4") (pinfunction "4_4") (pintype "passive"))
      (node (ref "R_CHANGE") (pin "2") (pinfunction "2_2") (pintype "passive"))
      (node (ref "U2") (pin "23") (pinfunction "IO15_23") (pintype "bidirectional"))
    )
    (net (code "19") (name "MISO") (class "Default")
      (node (ref "D12") (pin "2") (pinfunction "2_2") (pintype "passive"))
      (node (ref "J4") (pin "P7") (pinfunction "DAT0_P7") (pintype "bidirectional"))
      (node (ref "R8") (pin "1") (pinfunction "1_1") (pintype "passive"))
      (node (ref "TP6") (pin "TP") (pinfunction "TP_TP") (pintype "input"))
      (node (ref "U1") (pin "2") (pinfunction "DO(IO1)_2") (pintype "bidirectional"))
      (node (ref "U2") (pin "27") (pinfunction "IO2_27") (pintype "bidirectional"))
    )
    (net (code "20") (name "MOSI") (class "Default")
      (node (ref "D11") (pin "1") (pinfunction "1_1") (pintype "passive"))
      (node (ref "J1") (pin "14") (pinfunction "14_14") (pintype "bidirectional"))
      (node (ref "J4") (pin "P3") (pinfunction "CMD_P3") (pintype "bidirectional"))
      (node (ref "R7") (pin "1") (pinfunction "1_1") (pintype "passive"))
      (node (ref "TP7") (pin "TP") (pinfunction "TP_TP") (pintype "input"))
      (node (ref "U1") (pin "5") (pinfunction "DI(IO0)_5") (pintype "bidirectional"))
      (node (ref "U2") (pin "7") (pinfunction "IO7_7") (pintype "bidirectional"))
    )
    (net (code "21") (name "Net-(CHG_LED-PadC)") (class "Default")
      (node (ref "CHG_LED") (pin "C") (pinfunction "C_C") (pintype "passive"))
      (node (ref "R1_BAT") (pin "2") (pinfunction "2_2") (pintype "passive"))
    )
    (net (code "22") (name "Net-(D2-CATHODE)") (class "Default")
      (node (ref "C1_BAT1") (pin "1") (pinfunction "1_1") (pintype "passive"))
      (node (ref "D2") (pin "1") (pinfunction "CATHODE_1") (pintype "bidirectional"))
      (node (ref "IC4") (pin "1") (pinfunction "VIN_1") (pintype "bidirectional"))
      (node (ref "IC4") (pin "3") (pinfunction "CE_3") (pintype "bidirectional"))
      (node (ref "Q1") (pin "2") (pinfunction "S_2") (pintype "bidirectional"))
    )
    (net (code "23") (name "Net-(D3-A)") (class "Default")
      (node (ref "C4") (pin "1") (pinfunction "1_1") (pintype "passive"))
      (node (ref "D3") (pin "2") (pinfunction "A_2") (pintype "bidirectional"))
      (node (ref "D4") (pin "1") (pinfunction "K_1") (pintype "bidirectional"))
    )
    (net (code "24") (name "Net-(D7-CATHODE)") (class "Default")
      (node (ref "D7") (pin "1") (pinfunction "CATHODE_1") (pintype "bidirectional"))
      (node (ref "R_CAPACITOR") (pin "2") (pinfunction "2_2") (pintype "passive"))
    )
    (net (code "25") (name "Net-(EPD_C1-Pad1)") (class "Default")
      (node (ref "EPD_C1") (pin "1") (pinfunction "1_1") (pintype "passive"))
      (node (ref "J1") (pin "4") (pinfunction "4_4") (pintype "bidirectional"))
    )
    (net (code "26") (name "Net-(EPD_C2-Pad1)") (class "Default")
      (node (ref "EPD_C2") (pin "1") (pinfunction "1_1") (pintype "passive"))
      (node (ref "J1") (pin "5") (pinfunction "5_5") (pintype "bidirectional"))
    )
    (net (code "27") (name "Net-(EPD_C6-Pad1)") (class "Default")
      (node (ref "EPD_C6") (pin "1") (pinfunction "1_1") (pintype "passive"))
      (node (ref "J1") (pin "18") (pinfunction "18_18") (pintype "bidirectional"))
    )
    (net (code "28") (name "Net-(EPD_C7-Pad1)") (class "Default")
      (node (ref "EPD_C7") (pin "1") (pinfunction "1_1") (pintype "passive"))
      (node (ref "J1") (pin "19") (pinfunction "19_19") (pintype "bidirectional"))
    )
    (net (code "29") (name "Net-(EPD_C8-Pad1)") (class "Default")
      (node (ref "EPD_C8") (pin "1") (pinfunction "1_1") (pintype "passive"))
      (node (ref "J1") (pin "20") (pinfunction "20_20") (pintype "bidirectional"))
    )
    (net (code "30") (name "Net-(EPD_C10-Pad1)") (class "Default")
      (node (ref "EPD_C10") (pin "1") (pinfunction "1_1") (pintype "passive"))
      (node (ref "J1") (pin "22") (pinfunction "22_22") (pintype "bidirectional"))
    )
    (net (code "31") (name "Net-(EPD_C12-Pad1)") (class "Default")
      (node (ref "EPD_C12") (pin "1") (pinfunction "1_1") (pintype "passive"))
      (node (ref "J1") (pin "24") (pinfunction "24_24") (pintype "bidirectional"))
    )
    (net (code "32") (name "Net-(IC1-CT)") (class "Default")
      (node (ref "C_DELAY") (pin "1") (pinfunction "1_1") (pintype "passive"))
      (node (ref "IC1") (pin "5") (pinfunction "CT_5") (pintype "bidirectional"))
    )
    (net (code "33") (name "Net-(J2-PadA5)") (class "Default")
      (node (ref "J2") (pin "A5") (pinfunction "A5_A5") (pintype "bidirectional"))
      (node (ref "R2-USB1") (pin "2") (pinfunction "2_2") (pintype "passive"))
    )
    (net (code "34") (name "Net-(J2-PadB5)") (class "Default")
      (node (ref "J2") (pin "B5") (pinfunction "B5_B5") (pintype "bidirectional"))
      (node (ref "R2-USB") (pin "1") (pinfunction "1_1") (pintype "passive"))
    )
    (net (code "35") (name "Net-(MCP73831-PROG)") (class "Default")
      (node (ref "MCP73831") (pin "5") (pinfunction "PROG_5") (pintype "input"))
      (node (ref "R2_BAT") (pin "2") (pinfunction "2_2") (pintype "passive"))
    )
    (net (code "36") (name "Net-(MCP73831-STAT)") (class "Default")
      (node (ref "MCP73831") (pin "1") (pinfunction "STAT_1") (pintype "output"))
      (node (ref "R1_BAT") (pin "1") (pinfunction "1_1") (pintype "passive"))
    )
    (net (code "37") (name "PREVGH") (class "Default")
      (node (ref "D5") (pin "1") (pinfunction "K_1") (pintype "bidirectional"))
      (node (ref "EPD_C9") (pin "1") (pinfunction "1_1") (pintype "passive"))
      (node (ref "J1") (pin "21") (pinfunction "21_21") (pintype "bidirectional"))
    )
    (net (code "38") (name "PREVGL") (class "Default")
      (node (ref "D4") (pin "2") (pinfunction "A_2") (pintype "bidirectional"))
      (node (ref "EPD_C11") (pin "1") (pinfunction "1_1") (pintype "passive"))
      (node (ref "J1") (pin "23") (pinfunction "23_23") (pintype "bidirectional"))
    )
    (net (code "39") (name "RESE") (class "Default")
      (node (ref "J1") (pin "3") (pinfunction "3_3") (pintype "bidirectional"))
      (node (ref "Q3") (pin "2") (pinfunction "S_2") (pintype "bidirectional"))
      (node (ref "R3") (pin "1") (pinfunction "1_1") (pintype "passive"))
    )
    (net (code "40") (name "RESE'") (class "Default")
      (node (ref "R3") (pin "2") (pinfunction "2_2") (pintype "passive"))
      (node (ref "SJ1") (pin "2") (pinfunction "2_2") (pintype "passive"))
    )
    (net (code "41") (name "RESET") (class "Default")
      (node (ref "C5") (pin "1") (pinfunction "1_1") (pintype "passive"))
      (node (ref "IC1") (pin "1") (pinfunction "VOUT_1") (pintype "bidirectional"))
      (node (ref "RESET_BUTTON") (pin "3") (pinfunction "3_3") (pintype "passive"))
      (node (ref "RESET_BUTTON") (pin "4") (pinfunction "4_4") (pintype "passive"))
      (node (ref "R_RESET") (pin "2") (pinfunction "2_2") (pintype "passive"))
      (node (ref "U2") (pin "3") (pinfunction "EN_3") (pintype "input"))
    )
    (net (code "42") (name "RTC_RST") (class "Default")
      (node (ref "U2") (pin "16") (pinfunction "IO18_16") (pintype "bidirectional"))
      (node (ref "U3") (pin "4") (pinfunction "~{RST}_4") (pintype "input"))
    )
    (net (code "43") (name "RX") (class "Default")
      (node (ref "TP2") (pin "TP") (pinfunction "TP_TP") (pintype "input"))
      (node (ref "U2") (pin "24") (pinfunction "RXD0/GPIO17_24") (pintype "bidirectional"))
    )
    (net (code "44") (name "SCK") (class "Default")
      (node (ref "D10") (pin "1") (pinfunction "1_1") (pintype "passive"))
      (node (ref "J1") (pin "13") (pinfunction "13_13") (pintype "bidirectional"))
      (node (ref "J4") (pin "P5") (pinfunction "CLK_P5") (pintype "bidirectional"))
      (node (ref "R6") (pin "1") (pinfunction "1_1") (pintype "passive"))
      (node (ref "TP8") (pin "TP") (pinfunction "TP_TP") (pintype "input"))
      (node (ref "U1") (pin "6") (pinfunction "CLK_6") (pintype "input"))
      (node (ref "U2") (pin "6") (pinfunction "IO6_6") (pintype "bidirectional"))
    )
    (net (code "45") (name "SCL") (class "Default")
      (node (ref "J3") (pin "4") (pinfunction "4_4") (pintype "passive"))
      (node (ref "R2_PINH") (pin "1") (pinfunction "1_1") (pintype "passive"))
      (node (ref "SENSOR2") (pin "4") (pinfunction "SCK_4") (pintype "input"))
      (node (ref "U2") (pin "20") (pinfunction "IO22_20") (pintype "bidirectional"))
      (node (ref "U3") (pin "16") (pinfunction "SCL_16") (pintype "input"))
      (node (ref "U4") (pin "7") (pinfunction "SCL_7") (pintype "input"))
    )
    (net (code "46") (name "SDA") (class "Default")
      (node (ref "J3") (pin "3") (pinfunction "3_3") (pintype "passive"))
      (node (ref "R1_PINH") (pin "1") (pinfunction "1_1") (pintype "passive"))
      (node (ref "SENSOR2") (pin "3") (pinfunction "SDI_3") (pintype "bidirectional"))
      (node (ref "U2") (pin "19") (pinfunction "IO21_19") (pintype "bidirectional"))
      (node (ref "U3") (pin "15") (pinfunction "SDA_15") (pintype "bidirectional"))
      (node (ref "U4") (pin "8") (pinfunction "SDA_8") (pintype "bidirectional"))
    )
    (net (code "47") (name "SRC") (class "Default")
      (node (ref "C4") (pin "2") (pinfunction "2_2") (pintype "passive"))
      (node (ref "D5") (pin "2") (pinfunction "A_2") (pintype "bidirectional"))
      (node (ref "L1") (pin "1") (pinfunction "1_1") (pintype "passive"))
      (node (ref "Q3") (pin "3") (pinfunction "D_3") (pintype "bidirectional"))
    )
    (net (code "48") (name "SS_SD") (class "Default")
      (node (ref "D8") (pin "1") (pinfunction "1_1") (pintype "passive"))
      (node (ref "J4") (pin "P2") (pinfunction "CD/DAT3_P2") (pintype "bidirectional"))
      (node (ref "R10") (pin "1") (pinfunction "1_1") (pintype "passive"))
      (node (ref "U2") (pin "4") (pinfunction "IO4_4") (pintype "bidirectional"))
    )
    (net (code "49") (name "TX") (class "Default")
      (node (ref "TP1") (pin "TP") (pinfunction "TP_TP") (pintype "input"))
      (node (ref "U2") (pin "25") (pinfunction "TXD0/GPIO16_25") (pintype "bidirectional"))
    )
    (net (code "50") (name "USB_D+") (class "Default")
      (node (ref "D1") (pin "1") (pinfunction "I/O1_1_1") (pintype "bidirectional"))
      (node (ref "U2") (pin "14") (pinfunction "IO13_14") (pintype "bidirectional"))
    )
    (net (code "51") (name "USB_D-") (class "Default")
      (node (ref "D1") (pin "3") (pinfunction "I/O2_1_3") (pintype "bidirectional"))
      (node (ref "U2") (pin "13") (pinfunction "IO12_13") (pintype "bidirectional"))
    )
    (net (code "52") (name "VBAT") (class "Default")
      (node (ref "C2_BAT") (pin "1") (pinfunction "1_1") (pintype "passive"))
      (node (ref "MCP73831") (pin "3") (pinfunction "VBAT_3") (pintype "power_in"))
      (node (ref "Q1") (pin "3") (pinfunction "D_3") (pintype "bidirectional"))
      (node (ref "TP3") (pin "TP") (pinfunction "TP_TP") (pintype "input"))
      (node (ref "U4") (pin "2") (pinfunction "CELL_2") (pintype "power_in"))
      (node (ref "U4") (pin "3") (pinfunction "VDD_3") (pintype "power_in"))
    )
    (net (code "53") (name "VBUS") (class "Default")
      (node (ref "C1_BAT") (pin "1") (pinfunction "1_1") (pintype "passive"))
      (node (ref "C4_USB") (pin "1") (pinfunction "1_1") (pintype "passive"))
      (node (ref "C5_USB") (pin "1") (pinfunction "1_1") (pintype "passive"))
      (node (ref "CHG_LED") (pin "A") (pinfunction "A_A") (pintype "passive"))
      (node (ref "D1") (pin "5") (pinfunction "VBUS_5") (pintype "bidirectional"))
      (node (ref "D2") (pin "2") (pinfunction "ANODE_2") (pintype "bidirectional"))
      (node (ref "MCP73831") (pin "4") (pinfunction "VIN_4") (pintype "power_in"))
      (node (ref "PFMF.050.1") (pin "2") (pinfunction "2_2") (pintype "passive"))
      (node (ref "Q1") (pin "1") (pinfunction "G_1") (pintype "bidirectional"))
      (node (ref "R1_PWRUSB") (pin "2") (pinfunction "2_2") (pintype "passive"))
      (node (ref "TP14") (pin "TP") (pinfunction "TP_TP") (pintype "input"))
    )
    (net (code "54") (name "VRTC") (class "Default")
      (node (ref "C10_SUPERCAP") (pin "2") (pinfunction "2_2") (pintype "passive"))
      (node (ref "C8") (pin "1") (pinfunction "1_1") (pintype "passive"))
      (node (ref "R_CAPACITOR") (pin "1") (pinfunction "1_1") (pintype "passive"))
      (node (ref "U3") (pin "14") (pinfunction "VBAT_14") (pintype "power_in"))
    )
    (net (code "55") (name "VUSB") (class "Default")
      (node (ref "J2") (pin "A4") (pinfunction "A4_A4") (pintype "bidirectional"))
      (node (ref "J2") (pin "A9") (pinfunction "A9_A9") (pintype "bidirectional"))
      (node (ref "J2") (pin "B4") (pinfunction "B4_B4") (pintype "bidirectional"))
      (node (ref "J2") (pin "B9") (pinfunction "B9_B9") (pintype "bidirectional"))
      (node (ref "PFMF.050.1") (pin "1") (pinfunction "1_1") (pintype "passive"))
    )
    (net (code "56") (name "unconnected-(IC1-NC-Pad4)") (class "Default")
      (node (ref "IC1") (pin "4") (pinfunction "NC_4") (pintype "no_connect"))
    )
    (net (code "57") (name "unconnected-(IC4-NC-Pad4)") (class "Default")
      (node (ref "IC4") (pin "4") (pinfunction "NC_4") (pintype "no_connect"))
    )
    (net (code "58") (name "unconnected-(J1-Pad1)") (class "Default")
      (node (ref "J1") (pin "1") (pinfunction "1_1") (pintype "bidirectional"))
    )
    (net (code "59") (name "unconnected-(J1-Pad6)") (class "Default")
      (node (ref "J1") (pin "6") (pinfunction "6_6") (pintype "bidirectional"))
    )
    (net (code "60") (name "unconnected-(J1-Pad7)") (class "Default")
      (node (ref "J1") (pin "7") (pinfunction "7_7") (pintype "bidirectional"))
    )
    (net (code "61") (name "unconnected-(J2-PadA8)") (class "Default")
      (node (ref "J2") (pin "A8") (pinfunction "A8_A8") (pintype "bidirectional"))
    )
    (net (code "62") (name "unconnected-(J2-PadB8)") (class "Default")
      (node (ref "J2") (pin "B8") (pinfunction "B8_B8") (pintype "bidirectional"))
    )
    (net (code "63") (name "unconnected-(J4-DAT1-PadP8)") (class "Default")
      (node (ref "J4") (pin "P8") (pinfunction "DAT1_P8") (pintype "bidirectional"))
    )
    (net (code "64") (name "unconnected-(J4-DAT2-PadP1)") (class "Default")
      (node (ref "J4") (pin "P1") (pinfunction "DAT2_P1") (pintype "bidirectional"))
    )
    (net (code "65") (name "unconnected-(J4-DETECTION_1-PadS1)") (class "Default")
      (node (ref "J4") (pin "S1") (pinfunction "DETECTION_1_S1") (pintype "bidirectional"))
    )
    (net (code "66") (name "unconnected-(J4-DETECTION_2-PadS2)") (class "Default")
      (node (ref "J4") (pin "S2") (pinfunction "DETECTION_2_S2") (pintype "bidirectional"))
    )
    (net (code "67") (name "unconnected-(J4-VSS-PadP6)") (class "Default")
      (node (ref "J4") (pin "P6") (pinfunction "VSS_P6") (pintype "bidirectional"))
    )
    (net (code "68") (name "unconnected-(U2-NC-Pad22)") (class "Default")
      (node (ref "U2") (pin "22") (pinfunction "NC_22") (pintype "no_connect"))
    )
    (net (code "69") (name "unconnected-(U4-~{ALERT}-Pad5)") (class "Default")
      (node (ref "U4") (pin "5") (pinfunction "~{ALERT}_5") (pintype "output"))
    )
  )
)
